# top_level.net
KiCad netlist of a schematic drawn in Altium Designer
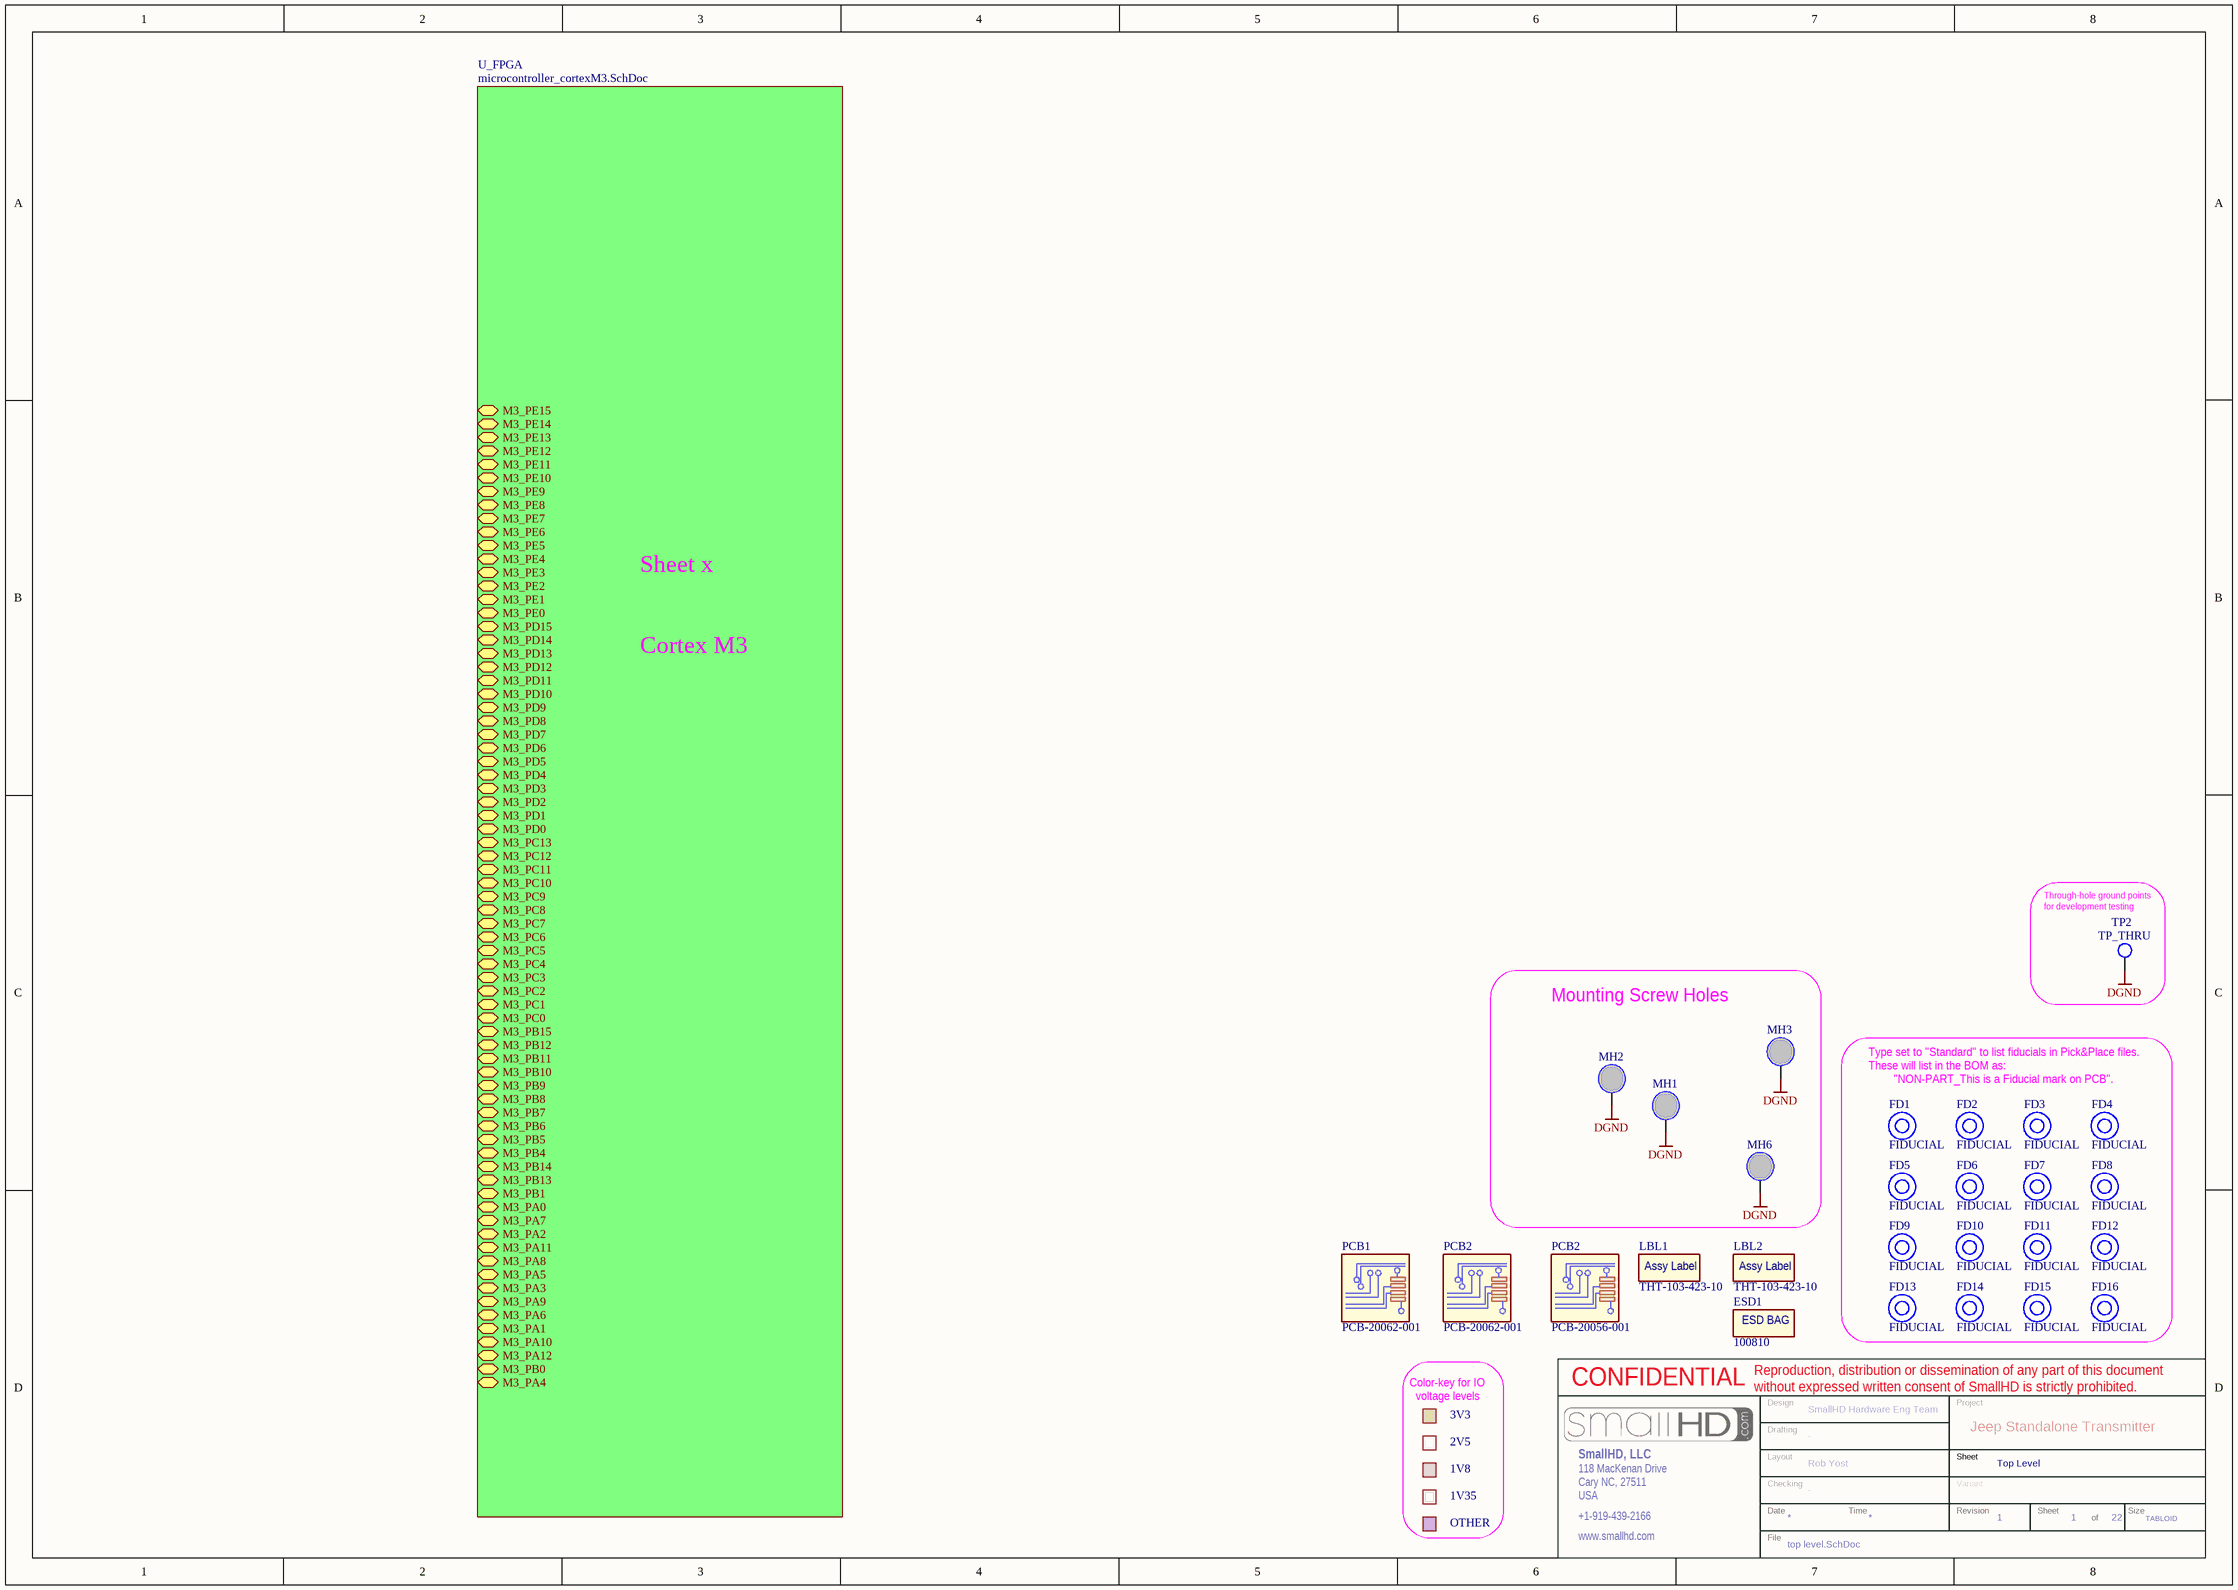
[diagram p0: top level.SchDoc]

(export (version "E")
  (design (tool "Eeschema 10.0.6"))
  (components
    (comp (ref "ESD1")
      (value "100810")
      (description "BAG STATIC METL-IN 8X10\" OPEN TOP")
      (fields (field (name "MANUFACTURER") "SCS"))
      (libsource (lib "smallHD") (part "ESDBAG_1"))
    )
    (comp (ref "FD1")
      (value "FIDUCIAL")
      (footprint "FID10X20")
      (description "NON-PART_This is a Fiducial mark on PCB")
      (libsource (lib "smallHD") (part "FIDUCIAL_BOMandPick&Place"))
    )
    (comp (ref "FD2")
      (value "FIDUCIAL")
      (footprint "FID10X20")
      (description "NON-PART_This is a Fiducial mark on PCB")
      (libsource (lib "smallHD") (part "FIDUCIAL_BOMandPick&Place"))
    )
    (comp (ref "FD3")
      (value "FIDUCIAL")
      (footprint "FID10X20")
      (description "NON-PART_This is a Fiducial mark on PCB")
      (libsource (lib "smallHD") (part "FIDUCIAL_BOMandPick&Place"))
    )
    (comp (ref "FD4")
      (value "FIDUCIAL")
      (footprint "FID10X20")
      (description "NON-PART_This is a Fiducial mark on PCB")
      (libsource (lib "smallHD") (part "FIDUCIAL_BOMandPick&Place"))
    )
    (comp (ref "FD5")
      (value "FIDUCIAL")
      (footprint "FID10X20")
      (description "NON-PART_This is a Fiducial mark on PCB")
      (libsource (lib "smallHD") (part "FIDUCIAL_BOMandPick&Place"))
    )
    (comp (ref "FD6")
      (value "FIDUCIAL")
      (footprint "FID10X20")
      (description "NON-PART_This is a Fiducial mark on PCB")
      (libsource (lib "smallHD") (part "FIDUCIAL_BOMandPick&Place"))
    )
    (comp (ref "FD7")
      (value "FIDUCIAL")
      (footprint "FID10X20")
      (description "NON-PART_This is a Fiducial mark on PCB")
      (libsource (lib "smallHD") (part "FIDUCIAL_BOMandPick&Place"))
    )
    (comp (ref "FD8")
      (value "FIDUCIAL")
      (footprint "FID10X20")
      (description "NON-PART_This is a Fiducial mark on PCB")
      (libsource (lib "smallHD") (part "FIDUCIAL_BOMandPick&Place"))
    )
    (comp (ref "FD9")
      (value "FIDUCIAL")
      (footprint "FID10X20")
      (description "NON-PART_This is a Fiducial mark on PCB")
      (libsource (lib "smallHD") (part "FIDUCIAL_BOMandPick&Place"))
    )
    (comp (ref "FD10")
      (value "FIDUCIAL")
      (footprint "FID10X20")
      (description "NON-PART_This is a Fiducial mark on PCB")
      (libsource (lib "smallHD") (part "FIDUCIAL_BOMandPick&Place"))
    )
    (comp (ref "FD11")
      (value "FIDUCIAL")
      (footprint "FID10X20")
      (description "NON-PART_This is a Fiducial mark on PCB")
      (libsource (lib "smallHD") (part "FIDUCIAL_BOMandPick&Place"))
    )
    (comp (ref "FD12")
      (value "FIDUCIAL")
      (footprint "FID10X20")
      (description "NON-PART_This is a Fiducial mark on PCB")
      (libsource (lib "smallHD") (part "FIDUCIAL_BOMandPick&Place"))
    )
    (comp (ref "FD13")
      (value "FIDUCIAL")
      (footprint "FID10X20")
      (description "NON-PART_This is a Fiducial mark on PCB")
      (libsource (lib "smallHD") (part "FIDUCIAL_BOMandPick&Place"))
    )
    (comp (ref "FD14")
      (value "FIDUCIAL")
      (footprint "FID10X20")
      (description "NON-PART_This is a Fiducial mark on PCB")
      (libsource (lib "smallHD") (part "FIDUCIAL_BOMandPick&Place"))
    )
    (comp (ref "FD15")
      (value "FIDUCIAL")
      (footprint "FID10X20")
      (description "NON-PART_This is a Fiducial mark on PCB")
      (libsource (lib "smallHD") (part "FIDUCIAL_BOMandPick&Place"))
    )
    (comp (ref "FD16")
      (value "FIDUCIAL")
      (footprint "FID10X20")
      (description "NON-PART_This is a Fiducial mark on PCB")
      (libsource (lib "smallHD") (part "FIDUCIAL_BOMandPick&Place"))
    )
    (comp (ref "LBL1")
      (value "THT-103-423-10")
      (footprint "Assembly_Label_LBL1")
      (description "LABEL 1.0 x 0.25 inch Thermal polyester")
      (fields (field (name "MANUFACTURER") "Brady"))
      (libsource (lib "smallHD") (part "LABEL_LBL1"))
    )
    (comp (ref "LBL2")
      (value "THT-103-423-10")
      (footprint "Assembly_Label_LBL2")
      (description "LABEL 1.0 x 0.25 inch Thermal polyester")
      (fields (field (name "MANUFACTURER") "Brady"))
      (libsource (lib "smallHD") (part "LABEL_LBL2"))
    )
    (comp (ref "MH1")
      (value "SCREW-HOLE")
      (footprint "M3_buttonhead_hex")
      (description "M3 x 0.5 mm Button-Head Socket Cap Screw 2 mm Hex")
      (libsource (lib "smallHD") (part "HOLE"))
    )
    (comp (ref "MH2")
      (value "SCREW-HOLE")
      (footprint "M3_buttonhead_hex")
      (description "M3 x 0.5 mm Button-Head Socket Cap Screw 2 mm Hex")
      (libsource (lib "smallHD") (part "HOLE"))
    )
    (comp (ref "MH3")
      (value "SCREW-HOLE")
      (footprint "M3_buttonhead_hex")
      (description "M3 x 0.5 mm Button-Head Socket Cap Screw 2 mm Hex")
      (libsource (lib "smallHD") (part "HOLE"))
    )
    (comp (ref "MH6")
      (value "SCREW-HOLE")
      (footprint "M3_buttonhead_hex")
      (description "M3 x 0.5 mm Button-Head Socket Cap Screw 2 mm Hex")
      (libsource (lib "smallHD") (part "HOLE"))
    )
    (comp (ref "PCB1")
      (value "PCB-20062-001")
      (footprint "LOGO_SmallHD_4")
      (description "PCB Jeep REV 001")
      (fields (field (name "MANUFACTURER") "PCB FAB"))
      (libsource (lib "smallHD") (part "PCB_1"))
    )
    (comp (ref "TP2")
      (value "TP_THRU")
      (footprint "TP_THRU_1")
      (description "Test Point - THRU")
      (libsource (lib "smallHD") (part "TP_1"))
    )
  )
  (nets
    (net (code "74") (name "DGND") (class "Default")
      (node (ref "MH1") (pin "1") (pinfunction "1_1") (pintype "passive"))
      (node (ref "MH2") (pin "1") (pinfunction "1_1") (pintype "passive"))
      (node (ref "MH3") (pin "1") (pinfunction "1_1") (pintype "passive"))
      (node (ref "MH6") (pin "1") (pinfunction "1_1") (pintype "passive"))
      (node (ref "TP2") (pin "1") (pinfunction "1_1") (pintype "passive"))
    )
    (net (code "75") (name "unconnected-(FD1-Pad0)") (class "Default")
      (node (ref "FD1") (pin "0") (pinfunction "0_0") (pintype "passive"))
    )
    (net (code "76") (name "unconnected-(FD2-Pad0)") (class "Default")
      (node (ref "FD2") (pin "0") (pinfunction "0_0") (pintype "passive"))
    )
    (net (code "77") (name "unconnected-(FD3-Pad0)") (class "Default")
      (node (ref "FD3") (pin "0") (pinfunction "0_0") (pintype "passive"))
    )
    (net (code "78") (name "unconnected-(FD4-Pad0)") (class "Default")
      (node (ref "FD4") (pin "0") (pinfunction "0_0") (pintype "passive"))
    )
    (net (code "79") (name "unconnected-(FD5-Pad0)") (class "Default")
      (node (ref "FD5") (pin "0") (pinfunction "0_0") (pintype "passive"))
    )
    (net (code "80") (name "unconnected-(FD6-Pad0)") (class "Default")
      (node (ref "FD6") (pin "0") (pinfunction "0_0") (pintype "passive"))
    )
    (net (code "81") (name "unconnected-(FD7-Pad0)") (class "Default")
      (node (ref "FD7") (pin "0") (pinfunction "0_0") (pintype "passive"))
    )
    (net (code "82") (name "unconnected-(FD8-Pad0)") (class "Default")
      (node (ref "FD8") (pin "0") (pinfunction "0_0") (pintype "passive"))
    )
    (net (code "83") (name "unconnected-(FD9-Pad0)") (class "Default")
      (node (ref "FD9") (pin "0") (pinfunction "0_0") (pintype "passive"))
    )
    (net (code "84") (name "unconnected-(FD10-Pad0)") (class "Default")
      (node (ref "FD10") (pin "0") (pinfunction "0_0") (pintype "passive"))
    )
    (net (code "85") (name "unconnected-(FD11-Pad0)") (class "Default")
      (node (ref "FD11") (pin "0") (pinfunction "0_0") (pintype "passive"))
    )
    (net (code "86") (name "unconnected-(FD12-Pad0)") (class "Default")
      (node (ref "FD12") (pin "0") (pinfunction "0_0") (pintype "passive"))
    )
    (net (code "87") (name "unconnected-(FD13-Pad0)") (class "Default")
      (node (ref "FD13") (pin "0") (pinfunction "0_0") (pintype "passive"))
    )
    (net (code "88") (name "unconnected-(FD14-Pad0)") (class "Default")
      (node (ref "FD14") (pin "0") (pinfunction "0_0") (pintype "passive"))
    )
    (net (code "89") (name "unconnected-(FD15-Pad0)") (class "Default")
      (node (ref "FD15") (pin "0") (pinfunction "0_0") (pintype "passive"))
    )
    (net (code "90") (name "unconnected-(FD16-Pad0)") (class "Default")
      (node (ref "FD16") (pin "0") (pinfunction "0_0") (pintype "passive"))
    )
  )
)
